# PDB_rev1.net
KiCad netlist of a schematic drawn in Altium Designer
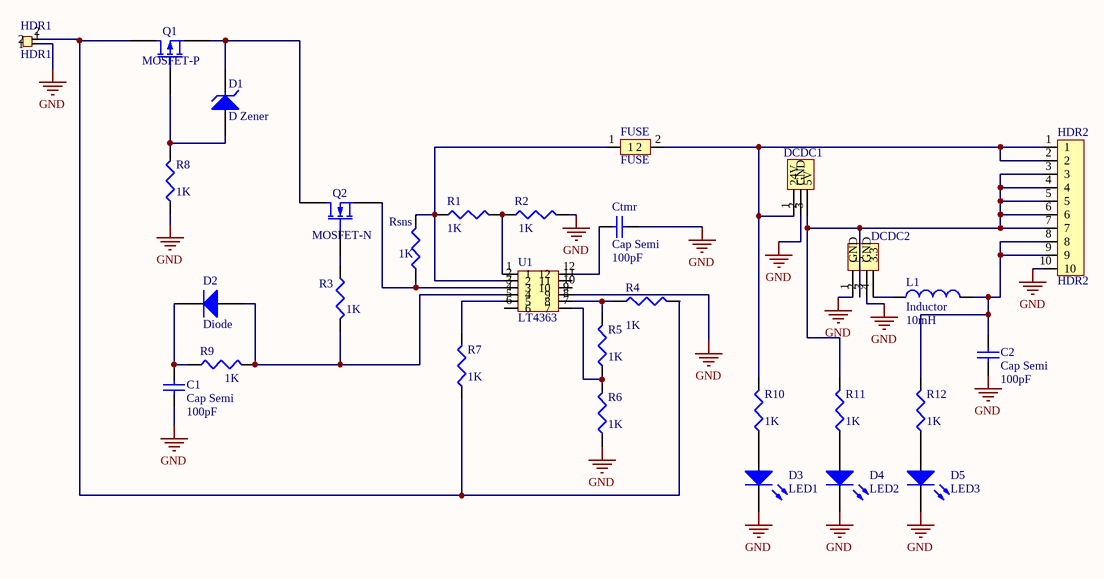
[diagram p0: PDB.rev1.SchDoc]

(export (version "E")
  (design (tool "Eeschema 10.0.6"))
  (components
    (comp (ref "C1")
      (value "Cap Semi")
      (footprint "C1206")
      (description "Capacitor (Semiconductor SIM Model)")
      (fields (field (name "ALTIUM_VALUE") "100pF") (field (name "PUBLISHER") "Altium Limited"))
      (libsource (lib "Miscellaneous Devices") (part "Cap Semi"))
    )
    (comp (ref "C2")
      (value "Cap Semi")
      (footprint "C1206")
      (description "Capacitor (Semiconductor SIM Model)")
      (fields (field (name "ALTIUM_VALUE") "100pF") (field (name "PUBLISHER") "Altium Limited"))
      (libsource (lib "Miscellaneous Devices") (part "Cap Semi"))
    )
    (comp (ref "Ctmr")
      (value "Cap Semi")
      (footprint "C1206")
      (description "Capacitor (Semiconductor SIM Model)")
      (fields (field (name "ALTIUM_VALUE") "100pF") (field (name "PUBLISHER") "Altium Limited"))
      (libsource (lib "Miscellaneous Devices") (part "Cap Semi"))
    )
    (comp (ref "D1")
      (value "D Zener")
      (footprint "LT4363:ZENER DIODE")
      (description "Zener Diode")
      (fields (field (name "PUBLISHER") "Altium Limited"))
      (libsource (lib "Miscellaneous Devices") (part "D Zener"))
    )
    (comp (ref "D2")
      (value "Diode")
      (footprint "LT4363:diode")
      (description "Default Diode")
      (fields (field (name "PUBLISHER") "Altium Limited"))
      (libsource (lib "Miscellaneous Devices") (part "Diode"))
    )
    (comp (ref "D3")
      (value "LED1")
      (footprint "LT4363:LED")
      (description "Typical BLUE SiC LED")
      (fields (field (name "PUBLISHER") "Altium Limited"))
      (libsource (lib "Miscellaneous Devices") (part "LED3"))
    )
    (comp (ref "D4")
      (value "LED2")
      (footprint "LT4363:LED")
      (description "Typical BLUE SiC LED")
      (fields (field (name "PUBLISHER") "Altium Limited"))
      (libsource (lib "Miscellaneous Devices") (part "LED3"))
    )
    (comp (ref "D5")
      (value "LED3")
      (footprint "LT4363:LED")
      (description "Typical BLUE SiC LED")
      (fields (field (name "PUBLISHER") "Altium Limited"))
      (libsource (lib "Miscellaneous Devices") (part "LED3"))
    )
    (comp (ref "DCDC1") (value "DCDC1") (footprint "DCDC1") (libsource (lib "LT4363") (part "DCDC1")))
    (comp (ref "DCDC2") (value "DCDC2") (footprint "DCDC2") (libsource (lib "LT4363") (part "DCDC2")))
    (comp (ref "FUSE") (value "FUSE") (footprint "FUSE") (libsource (lib "LT4363") (part "FUSE")))
    (comp (ref "HDR1") (value "HDR1") (footprint "HDR1") (libsource (lib "LT4363") (part "HDR1")))
    (comp (ref "HDR2") (value "HDR2") (footprint "HDR2") (libsource (lib "LT4363") (part "HDR2")))
    (comp (ref "L1")
      (value "Inductor")
      (footprint "0402-A")
      (fields (field (name "ALTIUM_VALUE") "10mH") (field (name "PUBLISHER") "Altium Limited"))
      (libsource (lib "Miscellaneous Devices") (part "Inductor"))
    )
    (comp (ref "Q1")
      (value "MOSFET-P")
      (footprint "LT4363:MOSFET")
      (description "P-Channel MOSFET")
      (fields (field (name "PUBLISHER") "Altium Limited"))
      (libsource (lib "Miscellaneous Devices") (part "MOSFET-P"))
    )
    (comp (ref "Q2")
      (value "MOSFET-N")
      (footprint "LT4363:MOSFET")
      (description "N-Channel MOSFET")
      (fields (field (name "PUBLISHER") "Altium Limited"))
      (libsource (lib "Miscellaneous Devices") (part "MOSFET-N"))
    )
    (comp (ref "R1")
      (value "1K")
      (footprint "J1-0603")
      (description "Resistor")
      (fields (field (name "PUBLISHER") "Altium Limited"))
      (libsource (lib "Miscellaneous Devices") (part "Res3"))
    )
    (comp (ref "R2")
      (value "1K")
      (footprint "J1-0603")
      (description "Resistor")
      (fields (field (name "PUBLISHER") "Altium Limited"))
      (libsource (lib "Miscellaneous Devices") (part "Res3"))
    )
    (comp (ref "R3")
      (value "1K")
      (footprint "J1-0603")
      (description "Resistor")
      (fields (field (name "PUBLISHER") "Altium Limited"))
      (libsource (lib "Miscellaneous Devices") (part "Res3"))
    )
    (comp (ref "R4")
      (value "1K")
      (footprint "J1-0603")
      (description "Resistor")
      (fields (field (name "PUBLISHER") "Altium Limited"))
      (libsource (lib "Miscellaneous Devices") (part "Res3"))
    )
    (comp (ref "R5")
      (value "1K")
      (footprint "J1-0603")
      (description "Resistor")
      (fields (field (name "PUBLISHER") "Altium Limited"))
      (libsource (lib "Miscellaneous Devices") (part "Res3"))
    )
    (comp (ref "R6")
      (value "1K")
      (footprint "J1-0603")
      (description "Resistor")
      (fields (field (name "PUBLISHER") "Altium Limited"))
      (libsource (lib "Miscellaneous Devices") (part "Res3"))
    )
    (comp (ref "R7")
      (value "1K")
      (footprint "J1-0603")
      (description "Resistor")
      (fields (field (name "PUBLISHER") "Altium Limited"))
      (libsource (lib "Miscellaneous Devices") (part "Res3"))
    )
    (comp (ref "R8")
      (value "1K")
      (footprint "J1-0603")
      (description "Resistor")
      (fields (field (name "PUBLISHER") "Altium Limited"))
      (libsource (lib "Miscellaneous Devices") (part "Res3"))
    )
    (comp (ref "R9")
      (value "1K")
      (footprint "J1-0603")
      (description "Resistor")
      (fields (field (name "PUBLISHER") "Altium Limited"))
      (libsource (lib "Miscellaneous Devices") (part "Res3"))
    )
    (comp (ref "R10")
      (value "1K")
      (footprint "J1-0603")
      (description "Resistor")
      (fields (field (name "PUBLISHER") "Altium Limited"))
      (libsource (lib "Miscellaneous Devices") (part "Res3"))
    )
    (comp (ref "R11")
      (value "1K")
      (footprint "J1-0603")
      (description "Resistor")
      (fields (field (name "PUBLISHER") "Altium Limited"))
      (libsource (lib "Miscellaneous Devices") (part "Res3"))
    )
    (comp (ref "R12")
      (value "1K")
      (footprint "J1-0603")
      (description "Resistor")
      (fields (field (name "PUBLISHER") "Altium Limited"))
      (libsource (lib "Miscellaneous Devices") (part "Res3"))
    )
    (comp (ref "Rsns")
      (value "1K")
      (footprint "J1-0603")
      (description "Resistor")
      (fields (field (name "PUBLISHER") "Altium Limited"))
      (libsource (lib "Miscellaneous Devices") (part "Res3"))
    )
    (comp (ref "U1") (value "LT4363") (footprint "LT4363") (libsource (lib "LT4363") (part "LT4363")))
  )
  (nets
    (net (code "1") (name "GND") (class "Default")
      (node (ref "C1") (pin "1") (pinfunction "1_1") (pintype "passive"))
      (node (ref "C2") (pin "1") (pinfunction "1_1") (pintype "passive"))
      (node (ref "Ctmr") (pin "1") (pinfunction "1_1") (pintype "passive"))
      (node (ref "D3") (pin "2") (pinfunction "K_2") (pintype "passive"))
      (node (ref "D4") (pin "2") (pinfunction "K_2") (pintype "passive"))
      (node (ref "D5") (pin "2") (pinfunction "K_2") (pintype "passive"))
      (node (ref "DCDC1") (pin "2") (pinfunction "GND_2") (pintype "passive"))
      (node (ref "DCDC2") (pin "1") (pinfunction "GND_1") (pintype "passive"))
      (node (ref "DCDC2") (pin "3") (pinfunction "GND_3") (pintype "passive"))
      (node (ref "HDR1") (pin "1") (pinfunction "1_1") (pintype "passive"))
      (node (ref "HDR2") (pin "10") (pinfunction "10_10") (pintype "passive"))
      (node (ref "R2") (pin "2") (pinfunction "2_2") (pintype "passive"))
      (node (ref "R6") (pin "1") (pinfunction "1_1") (pintype "passive"))
      (node (ref "R8") (pin "1") (pinfunction "1_1") (pintype "passive"))
      (node (ref "U1") (pin "9") (pinfunction "9_9") (pintype "passive"))
    )
    (net (code "2") (name "Net-(C2-Pad2)") (class "Default")
      (node (ref "C2") (pin "2") (pinfunction "2_2") (pintype "passive"))
      (node (ref "HDR2") (pin "8") (pinfunction "8_8") (pintype "passive"))
      (node (ref "HDR2") (pin "9") (pinfunction "9_9") (pintype "passive"))
      (node (ref "L1") (pin "2") (pinfunction "2_2") (pintype "passive"))
      (node (ref "R12") (pin "2") (pinfunction "2_2") (pintype "passive"))
    )
    (net (code "3") (name "Net-(Ctmr-Pad2)") (class "Default")
      (node (ref "Ctmr") (pin "2") (pinfunction "2_2") (pintype "passive"))
      (node (ref "U1") (pin "12") (pinfunction "12_12") (pintype "passive"))
    )
    (net (code "4") (name "Net-(D1-A)") (class "Default")
      (node (ref "D1") (pin "1") (pinfunction "A_1") (pintype "passive"))
      (node (ref "Q1") (pin "2") (pinfunction "G_2") (pintype "passive"))
      (node (ref "R8") (pin "2") (pinfunction "2_2") (pintype "passive"))
    )
    (net (code "5") (name "Net-(D1-K)") (class "Default")
      (node (ref "D1") (pin "2") (pinfunction "K_2") (pintype "passive"))
      (node (ref "Q1") (pin "3") (pinfunction "S_3") (pintype "passive"))
      (node (ref "Q2") (pin "1") (pinfunction "D_1") (pintype "passive"))
    )
    (net (code "6") (name "Net-(D2-A)") (class "Default")
      (node (ref "D2") (pin "1") (pinfunction "A_1") (pintype "passive"))
      (node (ref "R3") (pin "2") (pinfunction "2_2") (pintype "passive"))
      (node (ref "R9") (pin "2") (pinfunction "2_2") (pintype "passive"))
      (node (ref "U1") (pin "4") (pinfunction "4_4") (pintype "passive"))
    )
    (net (code "7") (name "Net-(D2-K)") (class "Default")
      (node (ref "C1") (pin "2") (pinfunction "2_2") (pintype "passive"))
      (node (ref "D2") (pin "2") (pinfunction "K_2") (pintype "passive"))
      (node (ref "R9") (pin "1") (pinfunction "1_1") (pintype "passive"))
    )
    (net (code "8") (name "Net-(D3-A)") (class "Default")
      (node (ref "D3") (pin "1") (pinfunction "A_1") (pintype "passive"))
      (node (ref "R10") (pin "1") (pinfunction "1_1") (pintype "passive"))
    )
    (net (code "9") (name "Net-(D4-A)") (class "Default")
      (node (ref "D4") (pin "1") (pinfunction "A_1") (pintype "passive"))
      (node (ref "R11") (pin "1") (pinfunction "1_1") (pintype "passive"))
    )
    (net (code "10") (name "Net-(D5-A)") (class "Default")
      (node (ref "D5") (pin "1") (pinfunction "A_1") (pintype "passive"))
      (node (ref "R12") (pin "1") (pinfunction "1_1") (pintype "passive"))
    )
    (net (code "11") (name "Net-(DCDC1-5V)") (class "Default")
      (node (ref "DCDC1") (pin "3") (pinfunction "5V_3") (pintype "passive"))
      (node (ref "DCDC2") (pin "2") (pinfunction "5_2") (pintype "passive"))
      (node (ref "HDR2") (pin "3") (pinfunction "3_3") (pintype "passive"))
      (node (ref "HDR2") (pin "4") (pinfunction "4_4") (pintype "passive"))
      (node (ref "HDR2") (pin "5") (pinfunction "5_5") (pintype "passive"))
      (node (ref "HDR2") (pin "6") (pinfunction "6_6") (pintype "passive"))
      (node (ref "HDR2") (pin "7") (pinfunction "7_7") (pintype "passive"))
      (node (ref "R11") (pin "2") (pinfunction "2_2") (pintype "passive"))
    )
    (net (code "12") (name "Net-(DCDC1-24V)") (class "Default")
      (node (ref "DCDC1") (pin "1") (pinfunction "24V_1") (pintype "passive"))
      (node (ref "FUSE") (pin "2") (pinfunction "2_2") (pintype "passive"))
      (node (ref "HDR2") (pin "1") (pinfunction "1_1") (pintype "passive"))
      (node (ref "HDR2") (pin "2") (pinfunction "2_2") (pintype "passive"))
      (node (ref "R10") (pin "2") (pinfunction "2_2") (pintype "passive"))
    )
    (net (code "13") (name "Net-(DCDC2-3.3)") (class "Default")
      (node (ref "DCDC2") (pin "4") (pinfunction "3.3_4") (pintype "passive"))
      (node (ref "L1") (pin "1") (pinfunction "1_1") (pintype "passive"))
    )
    (net (code "14") (name "Net-(FUSE-Pad1)") (class "Default")
      (node (ref "FUSE") (pin "1") (pinfunction "1_1") (pintype "passive"))
      (node (ref "R1") (pin "1") (pinfunction "1_1") (pintype "passive"))
      (node (ref "Rsns") (pin "2") (pinfunction "2_2") (pintype "passive"))
      (node (ref "U1") (pin "2") (pinfunction "2_2") (pintype "passive"))
    )
    (net (code "15") (name "Net-(Q1-D)") (class "Default")
      (node (ref "HDR1") (pin "2") (pinfunction "2_2") (pintype "passive"))
      (node (ref "Q1") (pin "1") (pinfunction "D_1") (pintype "passive"))
      (node (ref "R4") (pin "2") (pinfunction "2_2") (pintype "passive"))
      (node (ref "R7") (pin "1") (pinfunction "1_1") (pintype "passive"))
    )
    (net (code "16") (name "Net-(Q2-G)") (class "Default")
      (node (ref "Q2") (pin "2") (pinfunction "G_2") (pintype "passive"))
      (node (ref "R3") (pin "1") (pinfunction "1_1") (pintype "passive"))
    )
    (net (code "17") (name "Net-(Q2-S)") (class "Default")
      (node (ref "Q2") (pin "3") (pinfunction "S_3") (pintype "passive"))
      (node (ref "Rsns") (pin "1") (pinfunction "1_1") (pintype "passive"))
      (node (ref "U1") (pin "3") (pinfunction "3_3") (pintype "passive"))
    )
    (net (code "18") (name "Net-(R1-Pad2)") (class "Default")
      (node (ref "R1") (pin "2") (pinfunction "2_2") (pintype "passive"))
      (node (ref "R2") (pin "1") (pinfunction "1_1") (pintype "passive"))
      (node (ref "U1") (pin "1") (pinfunction "1_1") (pintype "passive"))
    )
    (net (code "19") (name "Net-(R4-Pad1)") (class "Default")
      (node (ref "R4") (pin "1") (pinfunction "1_1") (pintype "passive"))
      (node (ref "R5") (pin "2") (pinfunction "2_2") (pintype "passive"))
      (node (ref "U1") (pin "8") (pinfunction "8_8") (pintype "passive"))
    )
    (net (code "20") (name "Net-(R5-Pad1)") (class "Default")
      (node (ref "R5") (pin "1") (pinfunction "1_1") (pintype "passive"))
      (node (ref "R6") (pin "2") (pinfunction "2_2") (pintype "passive"))
      (node (ref "U1") (pin "7") (pinfunction "7_7") (pintype "passive"))
    )
    (net (code "21") (name "Net-(R7-Pad2)") (class "Default")
      (node (ref "R7") (pin "2") (pinfunction "2_2") (pintype "passive"))
      (node (ref "U1") (pin "5") (pinfunction "5_5") (pintype "passive"))
    )
    (net (code "22") (name "unconnected-(U1-Pad6)") (class "Default")
      (node (ref "U1") (pin "6") (pinfunction "6_6") (pintype "passive"))
    )
    (net (code "23") (name "unconnected-(U1-Pad10)") (class "Default")
      (node (ref "U1") (pin "10") (pinfunction "10_10") (pintype "passive"))
    )
    (net (code "24") (name "unconnected-(U1-Pad11)") (class "Default")
      (node (ref "U1") (pin "11") (pinfunction "11_11") (pintype "passive"))
    )
  )
)
